# main.net
KiCad netlist of a schematic drawn in EAGLE
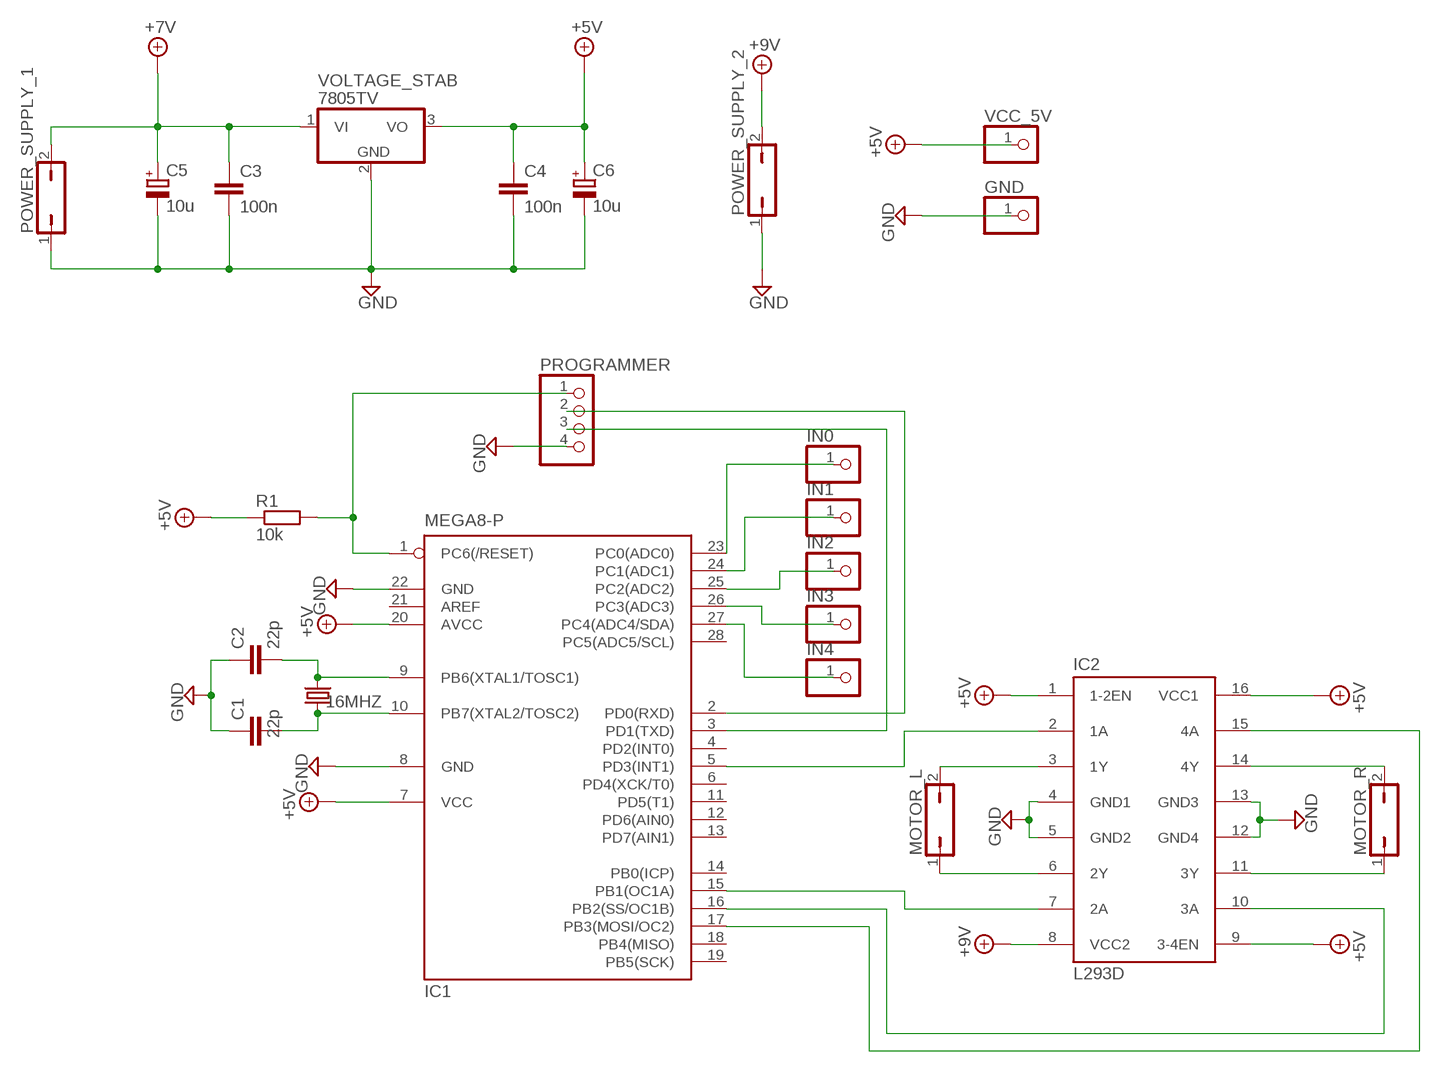
[diagram p0: schematic, sheet 1]

(export (version "E")
  (design (tool "Eeschema 10.0.6"))
  (components
    (comp (ref "16MHZ")
      (value "CRYSTALHC49S")
      (footprint "eagle-import:HC49_S")
      (libsource (lib "eagle-import") (part "CRYSTALHC49S"))
    )
    (comp (ref "C1")
      (value "22p")
      (footprint "eagle-import:C025-030X050")
      (libsource (lib "eagle-import") (part "C-EU025-030X050"))
    )
    (comp (ref "C2")
      (value "22p")
      (footprint "eagle-import:C025-030X050")
      (libsource (lib "eagle-import") (part "C-EU025-030X050"))
    )
    (comp (ref "C3")
      (value "100n")
      (footprint "eagle-import:C025-030X050")
      (libsource (lib "eagle-import") (part "C-EU025-030X050"))
    )
    (comp (ref "C4")
      (value "100n")
      (footprint "eagle-import:C025-030X050")
      (libsource (lib "eagle-import") (part "C-EU025-030X050"))
    )
    (comp (ref "C5")
      (value "10u")
      (footprint "eagle-import:E2,5-7")
      (libsource (lib "eagle-import") (part "CPOL-EUE2.5-7"))
    )
    (comp (ref "C6")
      (value "10u")
      (footprint "eagle-import:E2,5-7")
      (libsource (lib "eagle-import") (part "CPOL-EUE2.5-7"))
    )
    (comp (ref "GND")
      (value "PINHD-1X1")
      (footprint "eagle-import:1X01")
      (libsource (lib "eagle-import") (part "PINHD-1X1"))
    )
    (comp (ref "IC1")
      (value "MEGA8-P")
      (footprint "eagle-import:DIL28-3")
      (libsource (lib "eagle-import") (part "MEGA8-P"))
    )
    (comp (ref "IC2")
      (value "L293D")
      (footprint "eagle-import:DIL16")
      (libsource (lib "eagle-import") (part "L293D"))
    )
    (comp (ref "IN0")
      (value "PINHD-1X1")
      (footprint "eagle-import:1X01")
      (libsource (lib "eagle-import") (part "PINHD-1X1"))
    )
    (comp (ref "IN1")
      (value "PINHD-1X1")
      (footprint "eagle-import:1X01")
      (libsource (lib "eagle-import") (part "PINHD-1X1"))
    )
    (comp (ref "IN2")
      (value "PINHD-1X1")
      (footprint "eagle-import:1X01")
      (libsource (lib "eagle-import") (part "PINHD-1X1"))
    )
    (comp (ref "IN3")
      (value "PINHD-1X1")
      (footprint "eagle-import:1X01")
      (libsource (lib "eagle-import") (part "PINHD-1X1"))
    )
    (comp (ref "IN4")
      (value "PINHD-1X1")
      (footprint "eagle-import:1X01")
      (libsource (lib "eagle-import") (part "PINHD-1X1"))
    )
    (comp (ref "MOTOR_L")
      (value "JP1Q")
      (footprint "eagle-import:JP1")
      (libsource (lib "eagle-import") (part "JP1Q"))
    )
    (comp (ref "MOTOR_R")
      (value "JP1Q")
      (footprint "eagle-import:JP1")
      (libsource (lib "eagle-import") (part "JP1Q"))
    )
    (comp (ref "POWER_SUPPLY_1")
      (value "JP1Q")
      (footprint "eagle-import:JP1")
      (libsource (lib "eagle-import") (part "JP1Q"))
    )
    (comp (ref "POWER_SUPPLY_2")
      (value "JP1Q")
      (footprint "eagle-import:JP1")
      (libsource (lib "eagle-import") (part "JP1Q"))
    )
    (comp (ref "PROGRAMMER")
      (value "PINHD-1X4")
      (footprint "eagle-import:1X04")
      (libsource (lib "eagle-import") (part "PINHD-1X4"))
    )
    (comp (ref "R1")
      (value "10k")
      (footprint "eagle-import:0204_5")
      (libsource (lib "eagle-import") (part "R-EU_0204/5"))
    )
    (comp (ref "VCC_5V")
      (value "PINHD-1X1")
      (footprint "eagle-import:1X01")
      (libsource (lib "eagle-import") (part "PINHD-1X1"))
    )
    (comp (ref "VOLTAGE_STAB")
      (value "7805TV")
      (footprint "eagle-import:TO220V")
      (libsource (lib "eagle-import") (part "78TV05"))
    )
  )
  (nets
    (net (code "1") (name "+5V") (class "Default")
      (node (ref "C4") (pin "1") (pinfunction "1_1") (pintype "passive"))
      (node (ref "C6") (pin "+") (pinfunction "+_+") (pintype "passive"))
      (node (ref "IC1") (pin "20") (pinfunction "AVCC_20") (pintype "power_in"))
      (node (ref "IC1") (pin "7") (pinfunction "VCC_7") (pintype "power_in"))
      (node (ref "IC2") (pin "1") (pinfunction "1-2EN_1") (pintype "input"))
      (node (ref "IC2") (pin "16") (pinfunction "VCC1_16") (pintype "power_in"))
      (node (ref "IC2") (pin "9") (pinfunction "3-4EN_9") (pintype "input"))
      (node (ref "R1") (pin "1") (pinfunction "1_1") (pintype "passive"))
      (node (ref "VCC_5V") (pin "1") (pinfunction "1_1") (pintype "passive"))
      (node (ref "VOLTAGE_STAB") (pin "3") (pinfunction "VO_3") (pintype "passive"))
    )
    (net (code "2") (name "+7V") (class "Default")
      (node (ref "C3") (pin "1") (pinfunction "1_1") (pintype "passive"))
      (node (ref "C5") (pin "+") (pinfunction "+_+") (pintype "passive"))
      (node (ref "POWER_SUPPLY_1") (pin "2") (pinfunction "2_2") (pintype "passive"))
      (node (ref "VOLTAGE_STAB") (pin "1") (pinfunction "VI_1") (pintype "input"))
    )
    (net (code "3") (name "+9V") (class "Default")
      (node (ref "IC2") (pin "8") (pinfunction "VCC2_8") (pintype "power_in"))
      (node (ref "POWER_SUPPLY_2") (pin "2") (pinfunction "2_2") (pintype "passive"))
    )
    (net (code "4") (name "GND") (class "Default")
      (node (ref "C1") (pin "1") (pinfunction "1_1") (pintype "passive"))
      (node (ref "C2") (pin "1") (pinfunction "1_1") (pintype "passive"))
      (node (ref "C3") (pin "2") (pinfunction "2_2") (pintype "passive"))
      (node (ref "C4") (pin "2") (pinfunction "2_2") (pintype "passive"))
      (node (ref "C5") (pin "-") (pinfunction "-_-") (pintype "passive"))
      (node (ref "C6") (pin "-") (pinfunction "-_-") (pintype "passive"))
      (node (ref "GND") (pin "1") (pinfunction "1_1") (pintype "passive"))
      (node (ref "IC1") (pin "22") (pinfunction "GND_22") (pintype "power_in"))
      (node (ref "IC1") (pin "8") (pinfunction "GND_8") (pintype "power_in"))
      (node (ref "IC2") (pin "12") (pinfunction "GND4_12") (pintype "power_in"))
      (node (ref "IC2") (pin "13") (pinfunction "GND3_13") (pintype "power_in"))
      (node (ref "IC2") (pin "4") (pinfunction "GND1_4") (pintype "power_in"))
      (node (ref "IC2") (pin "5") (pinfunction "GND2_5") (pintype "power_in"))
      (node (ref "POWER_SUPPLY_1") (pin "1") (pinfunction "1_1") (pintype "passive"))
      (node (ref "POWER_SUPPLY_2") (pin "1") (pinfunction "1_1") (pintype "passive"))
      (node (ref "PROGRAMMER") (pin "4") (pinfunction "4_4") (pintype "passive"))
      (node (ref "VOLTAGE_STAB") (pin "2") (pinfunction "GND_2") (pintype "passive"))
    )
    (net (code "5") (name "Net-(IC1-PB1(OC1A))") (class "Default")
      (node (ref "IC1") (pin "15") (pinfunction "PB1(OC1A)_15") (pintype "bidirectional"))
      (node (ref "IC2") (pin "7") (pinfunction "2A_7") (pintype "input"))
    )
    (net (code "6") (name "Net-(IC1-PB2(SS{slash}OC1B))") (class "Default")
      (node (ref "IC1") (pin "16") (pinfunction "PB2(SS/OC1B)_16") (pintype "bidirectional"))
      (node (ref "IC2") (pin "10") (pinfunction "3A_10") (pintype "input"))
    )
    (net (code "7") (name "Net-(IC1-PB3(MOSI{slash}OC2))") (class "Default")
      (node (ref "IC1") (pin "17") (pinfunction "PB3(MOSI/OC2)_17") (pintype "bidirectional"))
      (node (ref "IC2") (pin "15") (pinfunction "4A_15") (pintype "input"))
    )
    (net (code "8") (name "Net-(IC1-PB6(XTAL1{slash}TOSC1))") (class "Default")
      (node (ref "16MHZ") (pin "2") (pinfunction "2_2") (pintype "passive"))
      (node (ref "C2") (pin "2") (pinfunction "2_2") (pintype "passive"))
      (node (ref "IC1") (pin "9") (pinfunction "PB6(XTAL1/TOSC1)_9") (pintype "bidirectional"))
    )
    (net (code "9") (name "Net-(IC1-PB7(XTAL2{slash}TOSC2))") (class "Default")
      (node (ref "16MHZ") (pin "1") (pinfunction "1_1") (pintype "passive"))
      (node (ref "C1") (pin "2") (pinfunction "2_2") (pintype "passive"))
      (node (ref "IC1") (pin "10") (pinfunction "PB7(XTAL2/TOSC2)_10") (pintype "bidirectional"))
    )
    (net (code "10") (name "Net-(IC1-PC0(ADC0))") (class "Default")
      (node (ref "IC1") (pin "23") (pinfunction "PC0(ADC0)_23") (pintype "bidirectional"))
      (node (ref "IN0") (pin "1") (pinfunction "1_1") (pintype "passive"))
    )
    (net (code "11") (name "Net-(IC1-PC1(ADC1))") (class "Default")
      (node (ref "IC1") (pin "24") (pinfunction "PC1(ADC1)_24") (pintype "bidirectional"))
      (node (ref "IN1") (pin "1") (pinfunction "1_1") (pintype "passive"))
    )
    (net (code "12") (name "Net-(IC1-PC2(ADC2))") (class "Default")
      (node (ref "IC1") (pin "25") (pinfunction "PC2(ADC2)_25") (pintype "bidirectional"))
      (node (ref "IN2") (pin "1") (pinfunction "1_1") (pintype "passive"))
    )
    (net (code "13") (name "Net-(IC1-PC3(ADC3))") (class "Default")
      (node (ref "IC1") (pin "26") (pinfunction "PC3(ADC3)_26") (pintype "bidirectional"))
      (node (ref "IN3") (pin "1") (pinfunction "1_1") (pintype "passive"))
    )
    (net (code "14") (name "Net-(IC1-PC4(ADC4{slash}SDA))") (class "Default")
      (node (ref "IC1") (pin "27") (pinfunction "PC4(ADC4/SDA)_27") (pintype "bidirectional"))
      (node (ref "IN4") (pin "1") (pinfunction "1_1") (pintype "passive"))
    )
    (net (code "15") (name "Net-(IC1-PC6({slash}RESET))") (class "Default")
      (node (ref "IC1") (pin "1") (pinfunction "PC6(/RESET)_1") (pintype "bidirectional"))
      (node (ref "PROGRAMMER") (pin "1") (pinfunction "1_1") (pintype "passive"))
      (node (ref "R1") (pin "2") (pinfunction "2_2") (pintype "passive"))
    )
    (net (code "16") (name "Net-(IC1-PD0(RXD))") (class "Default")
      (node (ref "IC1") (pin "2") (pinfunction "PD0(RXD)_2") (pintype "bidirectional"))
      (node (ref "PROGRAMMER") (pin "2") (pinfunction "2_2") (pintype "passive"))
    )
    (net (code "17") (name "Net-(IC1-PD1(TXD))") (class "Default")
      (node (ref "IC1") (pin "3") (pinfunction "PD1(TXD)_3") (pintype "bidirectional"))
      (node (ref "PROGRAMMER") (pin "3") (pinfunction "3_3") (pintype "passive"))
    )
    (net (code "18") (name "Net-(IC1-PD3(INT1))") (class "Default")
      (node (ref "IC1") (pin "5") (pinfunction "PD3(INT1)_5") (pintype "bidirectional"))
      (node (ref "IC2") (pin "2") (pinfunction "1A_2") (pintype "input"))
    )
    (net (code "19") (name "Net-(IC2-1Y)") (class "Default")
      (node (ref "IC2") (pin "3") (pinfunction "1Y_3") (pintype "output"))
      (node (ref "MOTOR_L") (pin "2") (pinfunction "2_2") (pintype "passive"))
    )
    (net (code "20") (name "Net-(IC2-2Y)") (class "Default")
      (node (ref "IC2") (pin "6") (pinfunction "2Y_6") (pintype "output"))
      (node (ref "MOTOR_L") (pin "1") (pinfunction "1_1") (pintype "passive"))
    )
    (net (code "21") (name "Net-(IC2-3Y)") (class "Default")
      (node (ref "IC2") (pin "11") (pinfunction "3Y_11") (pintype "output"))
      (node (ref "MOTOR_R") (pin "1") (pinfunction "1_1") (pintype "passive"))
    )
    (net (code "22") (name "Net-(IC2-4Y)") (class "Default")
      (node (ref "IC2") (pin "14") (pinfunction "4Y_14") (pintype "output"))
      (node (ref "MOTOR_R") (pin "2") (pinfunction "2_2") (pintype "passive"))
    )
    (net (code "23") (name "unconnected-(IC1-AREF-Pad21)") (class "Default")
      (node (ref "IC1") (pin "21") (pinfunction "AREF_21") (pintype "passive"))
    )
    (net (code "24") (name "unconnected-(IC1-PB0(ICP)-Pad14)") (class "Default")
      (node (ref "IC1") (pin "14") (pinfunction "PB0(ICP)_14") (pintype "bidirectional"))
    )
    (net (code "25") (name "unconnected-(IC1-PB4(MISO)-Pad18)") (class "Default")
      (node (ref "IC1") (pin "18") (pinfunction "PB4(MISO)_18") (pintype "bidirectional"))
    )
    (net (code "26") (name "unconnected-(IC1-PB5(SCK)-Pad19)") (class "Default")
      (node (ref "IC1") (pin "19") (pinfunction "PB5(SCK)_19") (pintype "bidirectional"))
    )
    (net (code "27") (name "unconnected-(IC1-PC5(ADC5{slash}SCL)-Pad28)") (class "Default")
      (node (ref "IC1") (pin "28") (pinfunction "PC5(ADC5/SCL)_28") (pintype "bidirectional"))
    )
    (net (code "28") (name "unconnected-(IC1-PD2(INT0)-Pad4)") (class "Default")
      (node (ref "IC1") (pin "4") (pinfunction "PD2(INT0)_4") (pintype "bidirectional"))
    )
    (net (code "29") (name "unconnected-(IC1-PD4(XCK{slash}T0)-Pad6)") (class "Default")
      (node (ref "IC1") (pin "6") (pinfunction "PD4(XCK/T0)_6") (pintype "bidirectional"))
    )
    (net (code "30") (name "unconnected-(IC1-PD5(T1)-Pad11)") (class "Default")
      (node (ref "IC1") (pin "11") (pinfunction "PD5(T1)_11") (pintype "bidirectional"))
    )
    (net (code "31") (name "unconnected-(IC1-PD6(AIN0)-Pad12)") (class "Default")
      (node (ref "IC1") (pin "12") (pinfunction "PD6(AIN0)_12") (pintype "bidirectional"))
    )
    (net (code "32") (name "unconnected-(IC1-PD7(AIN1)-Pad13)") (class "Default")
      (node (ref "IC1") (pin "13") (pinfunction "PD7(AIN1)_13") (pintype "bidirectional"))
    )
  )
)
